# PowerSupply.net
KiCad netlist of a schematic drawn in Altium Designer
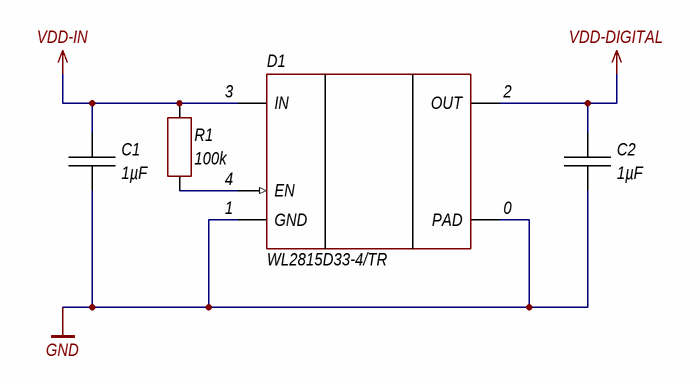
[diagram p0: PowerSupply.SchDoc]

(export (version "E")
  (design (tool "Eeschema 10.0.6"))
  (components
    (comp (ref "C1") (value "1µF") (footprint "CH0402C") (libsource (lib "Discrete") (part "Capacitor")))
    (comp (ref "C2") (value "1µF") (footprint "CH0402C") (libsource (lib "Discrete") (part "Capacitor")))
    (comp (ref "D1")
      (value "WL2815D33-4/TR")
      (footprint "DFN1010-4")
      (description "LDO")
      (libsource (lib "Power Supplies") (part "WL2815"))
    )
    (comp (ref "R1") (value "100k") (footprint "CH0402R") (libsource (lib "Discrete") (part "Resistor")))
  )
  (nets
    (net (code "1") (name "GND") (class "Default")
      (node (ref "C1") (pin "1") (pinfunction "1_1") (pintype "passive"))
      (node (ref "C2") (pin "1") (pinfunction "1_1") (pintype "passive"))
      (node (ref "D1") (pin "0") (pinfunction "PAD_0") (pintype "power_in"))
      (node (ref "D1") (pin "1") (pinfunction "GND_1") (pintype "power_in"))
    )
    (net (code "2") (name "Net-(D1-EN)") (class "Default")
      (node (ref "D1") (pin "4") (pinfunction "EN_4") (pintype "input"))
      (node (ref "R1") (pin "1") (pinfunction "1_1") (pintype "passive"))
    )
    (net (code "3") (name "VDD-DIGITAL") (class "Default")
      (node (ref "C2") (pin "2") (pinfunction "2_2") (pintype "passive"))
      (node (ref "D1") (pin "2") (pinfunction "OUT_2") (pintype "power_in"))
    )
    (net (code "4") (name "VDD-IN") (class "Default")
      (node (ref "C1") (pin "2") (pinfunction "2_2") (pintype "passive"))
      (node (ref "D1") (pin "3") (pinfunction "IN_3") (pintype "power_in"))
      (node (ref "R1") (pin "2") (pinfunction "2_2") (pintype "passive"))
    )
  )
)
